# Flash_memory.net
KiCad netlist of a schematic drawn in Altium Designer
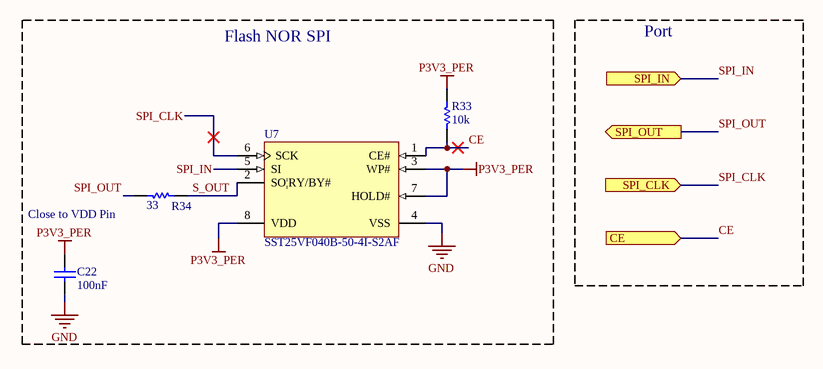
[diagram p0: Flash_memory.SchDoc]

(export (version "E")
  (design (tool "Eeschema 10.0.6"))
  (components
    (comp (ref "C22")
      (value "100nF")
      (footprint "0603C")
      (description "Capacitor 0402 / 0603 / 0805")
      (libsource (lib "MCD_TOOLS") (part "Capacitor_ST"))
    )
    (comp (ref "R33")
      (value "10k")
      (footprint "0603R")
      (description "Resistor")
      (fields (field (name "PUBLISHER") "Altium Limited"))
      (libsource (lib "Miscellaneous Devices") (part "Res1"))
    )
    (comp (ref "R34")
      (value "33")
      (footprint "0603R")
      (description "Resistor")
      (fields (field (name "PUBLISHER") "Altium Limited"))
      (libsource (lib "Miscellaneous Devices") (part "Res1"))
    )
    (comp (ref "U7")
      (value "SST25VF040B-50-4I-S2AF")
      (footprint "MCHP-SOIC-S2A8_N")
      (description "4 Mbit SPI Serial Flash, 2.7 to 3.6 V, 50 MHz, -40 to 85 degC, 8-pin SOIC (S2A8), Tube")
      (fields (field (name "MANUFACTURER") "Microchip"))
      (libsource (lib "Altium Content Vault") (part "MCHP-SST25VFXXXB-SOIX-8"))
    )
  )
  (nets
    (net (code "1") (name "/CE") (class "Default")
      (node (ref "R33") (pin "1") (pinfunction "1_1") (pintype "passive"))
      (node (ref "U7") (pin "1") (pinfunction "CE#_1") (pintype "input"))
    )
    (net (code "2") (name "/SPI_CLK") (class "Default")
      (node (ref "U7") (pin "6") (pinfunction "SCK_6") (pintype "input"))
    )
    (net (code "3") (name "/SPI_IN") (class "Default")
      (node (ref "U7") (pin "5") (pinfunction "SI_5") (pintype "input"))
    )
    (net (code "4") (name "/SPI_OUT") (class "Default")
      (node (ref "R34") (pin "1") (pinfunction "1_1") (pintype "passive"))
    )
    (net (code "5") (name "/S_OUT") (class "Default")
      (node (ref "R34") (pin "2") (pinfunction "2_2") (pintype "passive"))
      (node (ref "U7") (pin "2") (pinfunction "SO¦RY/BY#_2") (pintype "tri_state"))
    )
    (net (code "6") (name "GND") (class "Default")
      (node (ref "C22") (pin "1") (pinfunction "1_1") (pintype "passive"))
      (node (ref "U7") (pin "4") (pinfunction "VSS_4") (pintype "power_in"))
    )
    (net (code "7") (name "P3V3_PER") (class "Default")
      (node (ref "C22") (pin "2") (pinfunction "2_2") (pintype "passive"))
      (node (ref "R33") (pin "2") (pinfunction "2_2") (pintype "passive"))
      (node (ref "U7") (pin "3") (pinfunction "WP#_3") (pintype "input"))
      (node (ref "U7") (pin "7") (pinfunction "HOLD#_7") (pintype "input"))
      (node (ref "U7") (pin "8") (pinfunction "VDD_8") (pintype "power_in"))
    )
  )
)
